# design.net
KiCad netlist of a schematic drawn in Altium Designer
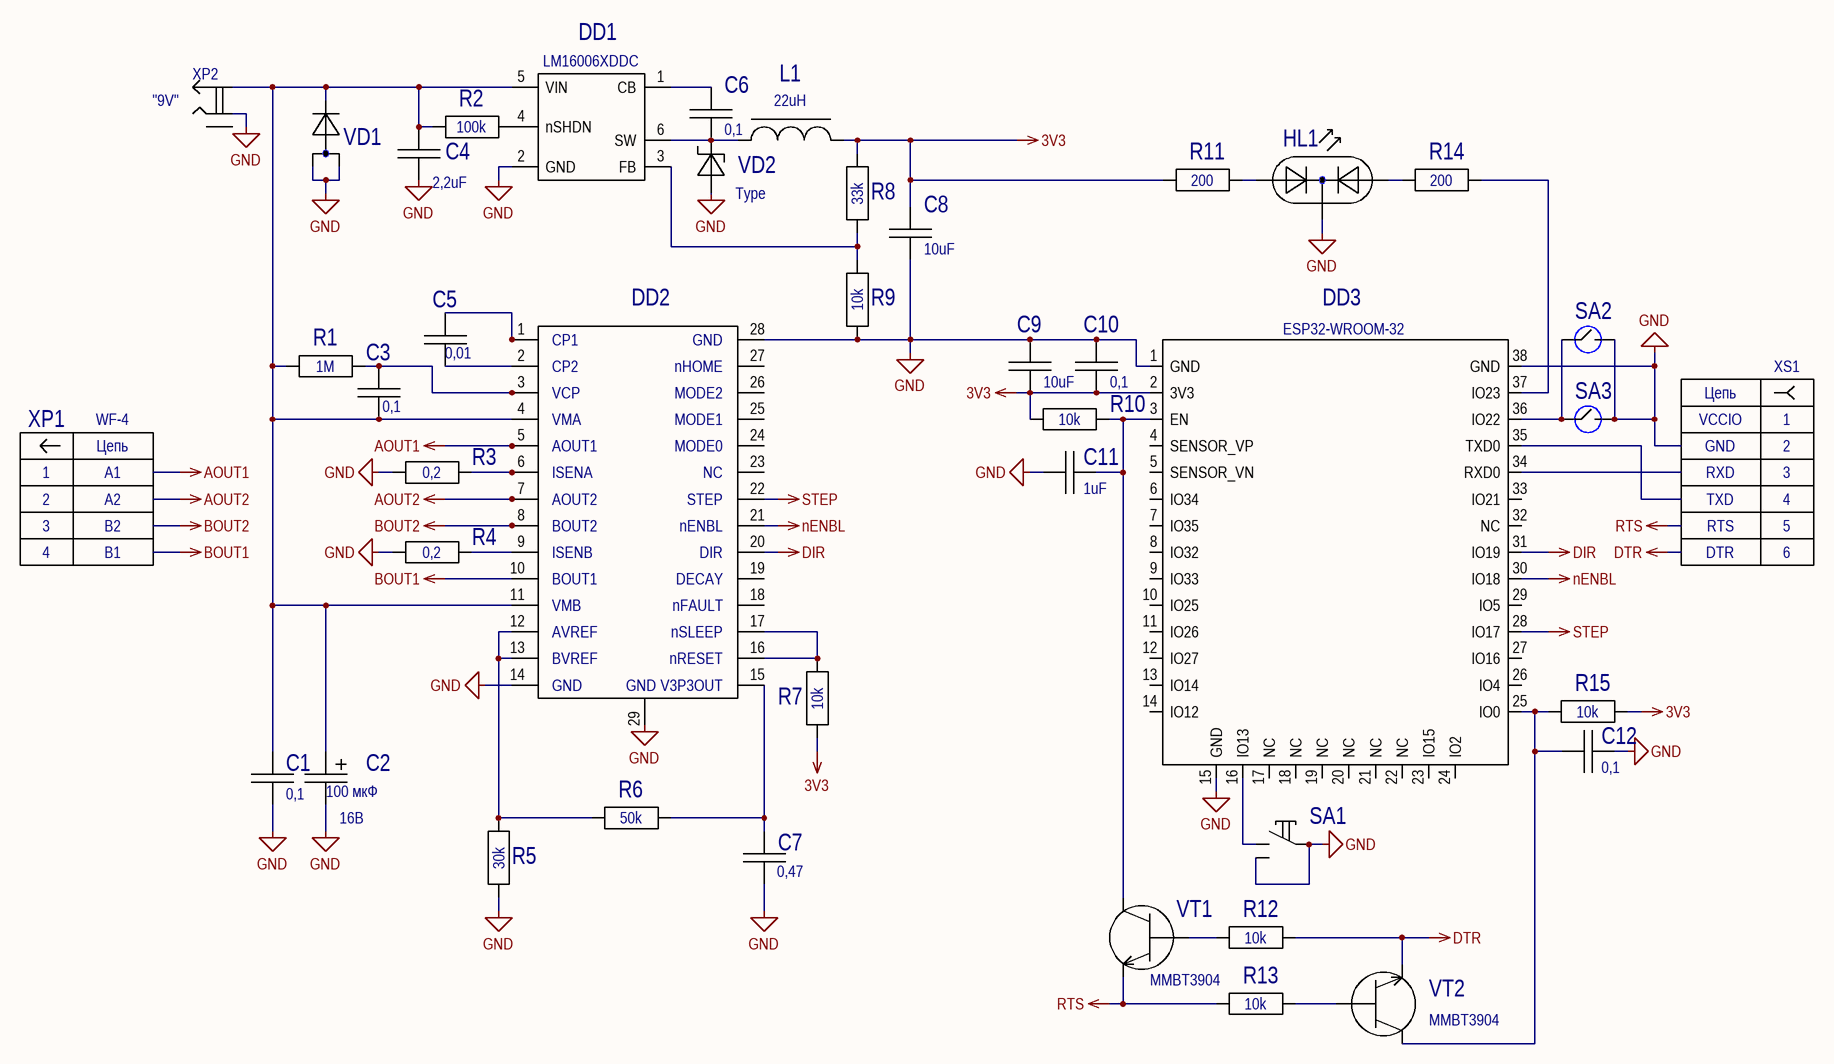
[diagram p0: Схема.SchDoc]

(export (version "E")
  (design (tool "Eeschema 10.0.6"))
  (components
    (comp (ref "C1")
      (value "0,1")
      (footprint "CAPC1608X09N")
      (fields
        (field (name "PART NUMBER") "Конденсатор 0.1мкФ X7R 50В 10% 0603, GRM188R71H104K")
        (field (name "Comment") "C0603")
      )
      (libsource (lib "my_lib") (part "C0603"))
    )
    (comp (ref "C2")
      (value "100 мкФ")
      (footprint "K53-68-E")
      (fields (field (name "VOLT") "16В") (field (name "Comment") "К53-68-E"))
      (libsource (lib "my_lib") (part "К53-68-E"))
    )
    (comp (ref "C3")
      (value "0,1")
      (footprint "CAPC1608X09N")
      (fields
        (field (name "PART NUMBER") "Конденсатор 0.1мкФ X7R 50В 10% 0603, GRM188R71H104K")
        (field (name "Comment") "C0603")
      )
      (libsource (lib "my_lib") (part "C0603"))
    )
    (comp (ref "C4")
      (value "2,2uF")
      (footprint "CAPC2012X14N")
      (fields
        (field (name "PART NUMBER") "Конденсатор 2.2мкФ X7R 25В 0805, GRM21BR71E225K")
        (field (name "Comment") "C0805")
      )
      (libsource (lib "my_lib") (part "C0805"))
    )
    (comp (ref "C5")
      (value "0,01")
      (footprint "CAPC1608X09N")
      (fields
        (field (name "PART NUMBER") "Конденсатор 0.01 мкФ X7R 50В 10% 0603, GRM188R71H103K")
        (field (name "Comment") "C0603")
      )
      (libsource (lib "my_lib") (part "C0603"))
    )
    (comp (ref "C6")
      (value "0,1")
      (footprint "CAPC1608X09N")
      (fields
        (field (name "PART NUMBER") "Конденсатор 0.1мкФ X7R 50В 10% 0603, GRM188R71H104K")
        (field (name "Comment") "C0603")
      )
      (libsource (lib "my_lib") (part "C0603"))
    )
    (comp (ref "C7")
      (value "0,47")
      (footprint "CAPC1608X09N")
      (fields
        (field (name "PART NUMBER") "Конденсатор CC0603KRX7R9BB474, 0603 X7R 0,47мкФ 50В 10%")
        (field (name "Comment") "C0603")
      )
      (libsource (lib "my_lib") (part "C0603"))
    )
    (comp (ref "C8")
      (value "10uF")
      (footprint "CAPC2012X14N")
      (fields
        (field (name "PART NUMBER") "Конденсатор 10 мкФ X5R 10% 16В 0805, GRM21BR61C106K")
        (field (name "Comment") "C0805")
      )
      (libsource (lib "my_lib") (part "C0805"))
    )
    (comp (ref "C9")
      (value "10uF")
      (footprint "CAPC2012X14N")
      (fields
        (field (name "PART NUMBER") "Конденсатор 10 мкФ X5R 10% 16В 0805, GRM21BR61C106K")
        (field (name "Comment") "C0805")
      )
      (libsource (lib "my_lib") (part "C0805"))
    )
    (comp (ref "C10")
      (value "0,1")
      (footprint "CAPC1608X09N")
      (fields
        (field (name "PART NUMBER") "Конденсатор 0.1мкФ X7R 50В 10% 0603, GRM188R71H104K")
        (field (name "Comment") "C0603")
      )
      (libsource (lib "my_lib") (part "C0603"))
    )
    (comp (ref "C11")
      (value "1uF")
      (footprint "CAPC1608X09N")
      (fields
        (field (name "PART NUMBER") "Конденсатор 1мкФ X7R 10В 10% 0603, GRM188R61A105K")
        (field (name "Comment") "C0603")
      )
      (libsource (lib "my_lib") (part "C0603"))
    )
    (comp (ref "C12")
      (value "0,1")
      (footprint "CAPC1608X09N")
      (fields
        (field (name "PART NUMBER") "Конденсатор 0.1мкФ X7R 50В 10% 0603, GRM188R71H104K")
        (field (name "Comment") "C0603")
      )
      (libsource (lib "my_lib") (part "C0603"))
    )
    (comp (ref "DD1")
      (value "LM16006")
      (footprint "TSOP95P280X110-6N")
      (description "LMR16006 SIMPLE SWITCHER® 60 V 0.6 A Buck Regulators")
      (fields
        (field (name "TYPE") "LM16006XDDC")
        (field (name "PART NUMBER") "Микросхема LM16006XDDC")
        (field (name "MANUFACTURER") "Texas Instruments")
      )
      (libsource (lib "my_lib") (part "LM16006XDDC"))
    )
    (comp (ref "DD2")
      (value "DRV8825")
      (footprint "TSOP65P640X120_HS-29N")
      (description "DRV8825 Stepper Motor Controller IC")
      (fields (field (name "PART NUMBER") "DRV8825PWP") (field (name "MANUFACTURER") "Texas Instruments"))
      (libsource (lib "my_lib") (part "DRV8825"))
    )
    (comp (ref "DD3")
      (value "Твердотельное реле 90В, 10А")
      (footprint "ESP32")
      (description "Модуль ESP32")
      (fields
        (field (name "PART NUMBER") "ESP32-WROOM-32D [16MB], Встраиваемый Wi-Fi/Bluetooth модуль на базе чипа ESP32-D0WD с PCB-антенной")
        (field (name "MANUFACTURER") "ESPRESSIV")
        (field (name "TYPE") "ESP32-WROOM-32")
      )
      (libsource (lib "my_lib") (part "ESP32-WROOM-32"))
    )
    (comp (ref "HL1")
      (value "LED3mm3pinCommonCatode")
      (footprint "LED3mm3pinCommonCatode")
      (fields (field (name "PART NUMBER") "Светодиод 3мм двухцветный с общим катодом"))
      (libsource (lib "my_lib") (part "LED3mm3pinCommonCatode"))
    )
    (comp (ref "L1")
      (value "22uH")
      (footprint "INDP7373X45N")
      (description "ЧИП-индуктивность силовая проволочная экранированная 22мкГн +20% 100кГц феррит 1.45А 91мОм")
      (fields
        (field (name "PART NUMBER") "Индуктивность 22uH, 1,45A B82472G6223M000")
        (field (name "Comment") "B82472G6223M000")
      )
      (libsource (lib "my_lib") (part "B82472G6223M000"))
    )
    (comp (ref "R1")
      (value "1M")
      (footprint "RESC1608X06N")
      (description "Резистор 0603")
      (fields (field (name "PART NUMBER") "Резистор 0.1Вт 0603 1 МОм, 5%") (field (name "Comment") "R0603"))
      (libsource (lib "my_lib") (part "R0603"))
    )
    (comp (ref "R2")
      (value "100k")
      (footprint "RESC1608X06N")
      (description "Резистор 0603")
      (fields (field (name "PART NUMBER") "Резистор 0.1Вт 0603 100 кОм, 5%") (field (name "Comment") "R0603"))
      (libsource (lib "my_lib") (part "R0603"))
    )
    (comp (ref "R3")
      (value "0,2")
      (footprint "RESC2012X07N")
      (description "Резистор шунт BOURNS 1W 1% 200 мОм")
      (fields
        (field (name "PART NUMBER") "Резистор 0805 0,2 Ом, 1% RI0805LR200FT")
        (field (name "Comment") "CRL2512-FWR200ELF")
      )
      (libsource (lib "my_lib") (part "CRL2512-FWR200ELF"))
    )
    (comp (ref "R4")
      (value "0,2")
      (footprint "RESC2012X07N")
      (description "Резистор шунт BOURNS 1W 1% 200 мОм")
      (fields
        (field (name "PART NUMBER") "Резистор 0805 0,2 Ом, 1% RI0805LR200FT")
        (field (name "Comment") "CRL2512-FWR200ELF")
      )
      (libsource (lib "my_lib") (part "CRL2512-FWR200ELF"))
    )
    (comp (ref "R5")
      (value "30k")
      (footprint "RESC1608X06N")
      (description "Резистор 0603")
      (fields (field (name "PART NUMBER") "Резистор 0.1Вт 0603 30 кОм, 1%") (field (name "Comment") "R0603"))
      (libsource (lib "my_lib") (part "R0603"))
    )
    (comp (ref "R6")
      (value "50k")
      (footprint "RESC1608X06N")
      (description "Резистор 0603")
      (fields (field (name "PART NUMBER") "Резистор 0.1Вт 0603 50 кОм, 1%") (field (name "Comment") "R0603"))
      (libsource (lib "my_lib") (part "R0603"))
    )
    (comp (ref "R7")
      (value "10k")
      (footprint "RESC1608X06N")
      (description "Резистор 0603")
      (fields (field (name "PART NUMBER") "Резистор 0.1Вт 0603 10 кОм, 5%") (field (name "Comment") "R0603"))
      (libsource (lib "my_lib") (part "R0603"))
    )
    (comp (ref "R8")
      (value "33k")
      (footprint "RESC1608X06N")
      (description "Резистор 0603")
      (fields (field (name "PART NUMBER") "Резистор 0.1Вт 0603 33 кОм, 1%") (field (name "Comment") "R0603"))
      (libsource (lib "my_lib") (part "R0603"))
    )
    (comp (ref "R9")
      (value "10k")
      (footprint "RESC1608X06N")
      (description "Резистор 0603")
      (fields (field (name "PART NUMBER") "Резистор 0.1Вт 0603 10 кОм, 1%") (field (name "Comment") "R0603"))
      (libsource (lib "my_lib") (part "R0603"))
    )
    (comp (ref "R10")
      (value "10k")
      (footprint "RESC1608X06N")
      (description "Резистор 0603")
      (fields (field (name "PART NUMBER") "Резистор 0.1Вт 0603 10 кОм, 5%") (field (name "Comment") "R0603"))
      (libsource (lib "my_lib") (part "R0603"))
    )
    (comp (ref "R11")
      (value "200")
      (footprint "RESC1608X06N")
      (description "Резистор 0603")
      (fields (field (name "PART NUMBER") "Резистор 0.1Вт 0603 200 Ом, 5%") (field (name "Comment") "R0603"))
      (libsource (lib "my_lib") (part "R0603"))
    )
    (comp (ref "R12")
      (value "10k")
      (footprint "RESC1608X06N")
      (description "Резистор 0603")
      (fields (field (name "PART NUMBER") "Резистор 0.1Вт 0603 10 кОм, 5%") (field (name "Comment") "R0603"))
      (libsource (lib "my_lib") (part "R0603"))
    )
    (comp (ref "R13")
      (value "10k")
      (footprint "RESC1608X06N")
      (description "Резистор 0603")
      (fields (field (name "PART NUMBER") "Резистор 0.1Вт 0603 10 кОм, 5%") (field (name "Comment") "R0603"))
      (libsource (lib "my_lib") (part "R0603"))
    )
    (comp (ref "R14")
      (value "200")
      (footprint "RESC1608X06N")
      (description "Резистор 0603")
      (fields (field (name "PART NUMBER") "Резистор 0.1Вт 0603 200 Ом, 5%") (field (name "Comment") "R0603"))
      (libsource (lib "my_lib") (part "R0603"))
    )
    (comp (ref "R15")
      (value "10k")
      (footprint "RESC1608X06N")
      (description "Резистор 0603")
      (fields (field (name "PART NUMBER") "Резистор 0.1Вт 0603 10 кОм, 5%") (field (name "Comment") "R0603"))
      (libsource (lib "my_lib") (part "R0603"))
    )
    (comp (ref "SA1")
      (value "Кнопка")
      (footprint "Кнопка 4,3х4,3 боковая")
      (description "Кнопка трехконтактная 4,5х4,5 боковая")
      (fields (field (name "PART NUMBER") "tact switch 4.5x4.5mm"))
      (libsource (lib "my_lib") (part "TactSwitch4.5x4.5"))
    )
    (comp (ref "SA2")
      (value "геркон 12мм")
      (footprint "Геркон 12 мм")
      (description "Геркон пластик Китай 12мм")
      (fields (field (name "PART NUMBER") "Геркон 12 мм"))
      (libsource (lib "my_lib") (part "геркон 12мм"))
    )
    (comp (ref "SA3")
      (value "геркон 12мм")
      (footprint "Геркон 12 мм")
      (description "Геркон пластик Китай 12мм")
      (fields (field (name "PART NUMBER") "Геркон 12 мм"))
      (libsource (lib "my_lib") (part "геркон 12мм"))
    )
    (comp (ref "VD1")
      (value "SS10PH10")
      (footprint "TO-277A")
      (description "High Current Density Surface-Mount\r\nHigh Voltage Schottky Rectifiers")
      (libsource (lib "my_lib") (part "SS10PH10"))
    )
    (comp (ref "VD2")
      (value "Диод Шоттки 40V, 500mA SOD123")
      (footprint "SODFL370X125-2N")
      (fields (field (name "TYPE") "Type") (field (name "PART NUMBER") "MBR0540"))
      (libsource (lib "my_lib") (part "MBR0540"))
    )
    (comp (ref "VT1")
      (value "MMBT3904")
      (footprint "SOT95P245X110-3N")
      (description "MMBT3904, Транзистор NPN 40В 0.2А [SOT-23-3]")
      (fields (field (name "TYPE") "MMBT3904") (field (name "PART NUMBER") "Транзистор MMBT3904"))
      (libsource (lib "my_lib") (part "MMBT3904"))
    )
    (comp (ref "VT2")
      (value "MMBT3904")
      (footprint "SOT95P245X110-3N")
      (description "MMBT3904, Транзистор NPN 40В 0.2А [SOT-23-3]")
      (fields (field (name "TYPE") "MMBT3904") (field (name "PART NUMBER") "Транзистор MMBT3904"))
      (libsource (lib "my_lib") (part "MMBT3904"))
    )
    (comp (ref "XP1")
      (value "WF4")
      (footprint "WF-4")
      (description "Вилка 2,54мм прямая на плату")
      (fields (field (name "TYPE") "WF-4") (field (name "PART NUMBER") "Вилка WF-4"))
      (libsource (lib "soed_new") (part "WF4_1"))
    )
    (comp (ref "XP2")
      (value "DC-005")
      (footprint "DC-005")
      (description "Разъем питания DC 2.1x5.5 мм гнездо, прямой угол на плату")
      (fields (field (name "PART NUMBER") "Вилка DS-201"))
      (libsource (lib "soed_new") (part "DC-005"))
    )
    (comp (ref "XS1")
      (value "PBS-6R")
      (footprint "PBS-6")
      (description "Розетка 2,54мм прямая однорядная на плату")
      (fields (field (name "PART NUMBER") "Розетка PBS-6"))
      (libsource (lib "soed_new") (part "PBS-6"))
    )
  )
  (nets
    (net (code "1") (name "3V3") (class "Default")
      (node (ref "C10") (pin "1") (pinfunction "1_1") (pintype "passive"))
      (node (ref "C8") (pin "1") (pinfunction "0_1") (pintype "passive"))
      (node (ref "C9") (pin "2") (pinfunction "1_2") (pintype "passive"))
      (node (ref "DD3") (pin "2") (pinfunction "3V3_2") (pintype "passive"))
      (node (ref "L1") (pin "1") (pinfunction "0_1") (pintype "passive"))
      (node (ref "R10") (pin "2") (pinfunction "2_2") (pintype "passive"))
      (node (ref "R11") (pin "2") (pinfunction "2_2") (pintype "passive"))
      (node (ref "R15") (pin "1") (pinfunction "1_1") (pintype "passive"))
      (node (ref "R7") (pin "1") (pinfunction "1_1") (pintype "passive"))
      (node (ref "R8") (pin "2") (pinfunction "2_2") (pintype "passive"))
    )
    (net (code "2") (name "AOUT1") (class "Default")
      (node (ref "DD2") (pin "5") (pinfunction "5_5") (pintype "passive"))
      (node (ref "XP1") (pin "1") (pinfunction "1_1") (pintype "passive"))
    )
    (net (code "3") (name "AOUT2") (class "Default")
      (node (ref "DD2") (pin "7") (pinfunction "7_7") (pintype "passive"))
      (node (ref "XP1") (pin "2") (pinfunction "2_2") (pintype "passive"))
    )
    (net (code "4") (name "BOUT1") (class "Default")
      (node (ref "DD2") (pin "10") (pinfunction "10_10") (pintype "passive"))
      (node (ref "XP1") (pin "4") (pinfunction "4_4") (pintype "passive"))
    )
    (net (code "5") (name "BOUT2") (class "Default")
      (node (ref "DD2") (pin "8") (pinfunction "8_8") (pintype "passive"))
      (node (ref "XP1") (pin "3") (pinfunction "3_3") (pintype "passive"))
    )
    (net (code "6") (name "DIR") (class "Default")
      (node (ref "DD2") (pin "20") (pinfunction "20_20") (pintype "passive"))
      (node (ref "DD3") (pin "31") (pinfunction "IO19_31") (pintype "passive"))
    )
    (net (code "7") (name "DTR") (class "Default")
      (node (ref "R12") (pin "2") (pinfunction "2_2") (pintype "passive"))
      (node (ref "VT2") (pin "2") (pinfunction "E_2") (pintype "passive"))
      (node (ref "XS1") (pin "6") (pinfunction "6_6") (pintype "passive"))
    )
    (net (code "8") (name "GND") (class "Default")
      (node (ref "C1") (pin "1") (pinfunction "1_1") (pintype "passive"))
      (node (ref "C10") (pin "2") (pinfunction "2_2") (pintype "passive"))
      (node (ref "C11") (pin "1") (pinfunction "1_1") (pintype "passive"))
      (node (ref "C12") (pin "2") (pinfunction "2_2") (pintype "passive"))
      (node (ref "C2") (pin "2") (pinfunction "2_2") (pintype "passive"))
      (node (ref "C4") (pin "2") (pinfunction "1_2") (pintype "passive"))
      (node (ref "C7") (pin "2") (pinfunction "2_2") (pintype "passive"))
      (node (ref "C8") (pin "2") (pinfunction "1_2") (pintype "passive"))
      (node (ref "C9") (pin "1") (pinfunction "0_1") (pintype "passive"))
      (node (ref "DD1") (pin "2") (pinfunction "GND_2") (pintype "passive"))
      (node (ref "DD2") (pin "14") (pinfunction "14_14") (pintype "passive"))
      (node (ref "DD2") (pin "28") (pinfunction "28_28") (pintype "passive"))
      (node (ref "DD2") (pin "29") (pinfunction "29_29") (pintype "passive"))
      (node (ref "DD3") (pin "1") (pinfunction "GND_1") (pintype "passive"))
      (node (ref "DD3") (pin "15") (pinfunction "GND_15") (pintype "passive"))
      (node (ref "DD3") (pin "38") (pinfunction "GND_38") (pintype "passive"))
      (node (ref "HL1") (pin "3") (pinfunction "C_3") (pintype "passive"))
      (node (ref "R3") (pin "1") (pinfunction "1_1") (pintype "passive"))
      (node (ref "R4") (pin "1") (pinfunction "1_1") (pintype "passive"))
      (node (ref "R5") (pin "1") (pinfunction "1_1") (pintype "passive"))
      (node (ref "R9") (pin "1") (pinfunction "1_1") (pintype "passive"))
      (node (ref "SA1") (pin "1") (pinfunction "1_1") (pintype "passive"))
      (node (ref "SA1") (pin "3") (pinfunction "3_3") (pintype "passive"))
      (node (ref "SA2") (pin "2") (pinfunction "2_2") (pintype "passive"))
      (node (ref "SA3") (pin "2") (pinfunction "2_2") (pintype "passive"))
      (node (ref "VD1") (pin "1") (pinfunction "A1_1") (pintype "passive"))
      (node (ref "VD1") (pin "2") (pinfunction "A2_2") (pintype "passive"))
      (node (ref "VD2") (pin "1") (pinfunction "1_1") (pintype "passive"))
      (node (ref "XP2") (pin "2") (pinfunction "2_2") (pintype "passive"))
      (node (ref "XS1") (pin "2") (pinfunction "2_2") (pintype "passive"))
    )
    (net (code "9") (name "Net-(C3-Pad2)") (class "Default")
      (node (ref "C3") (pin "2") (pinfunction "2_2") (pintype "passive"))
      (node (ref "DD2") (pin "3") (pinfunction "3_3") (pintype "passive"))
      (node (ref "R1") (pin "2") (pinfunction "2_2") (pintype "passive"))
    )
    (net (code "10") (name "Net-(C4-0)") (class "Default")
      (node (ref "C1") (pin "2") (pinfunction "2_2") (pintype "passive"))
      (node (ref "C2") (pin "1") (pinfunction "1_1") (pintype "passive"))
      (node (ref "C3") (pin "1") (pinfunction "1_1") (pintype "passive"))
      (node (ref "C4") (pin "1") (pinfunction "0_1") (pintype "passive"))
      (node (ref "DD1") (pin "5") (pinfunction "VIN_5") (pintype "passive"))
      (node (ref "DD2") (pin "11") (pinfunction "11_11") (pintype "passive"))
      (node (ref "DD2") (pin "4") (pinfunction "4_4") (pintype "passive"))
      (node (ref "R1") (pin "1") (pinfunction "1_1") (pintype "passive"))
      (node (ref "R2") (pin "1") (pinfunction "1_1") (pintype "passive"))
      (node (ref "VD1") (pin "3") (pinfunction "C_3") (pintype "passive"))
      (node (ref "XP2") (pin "1") (pinfunction "1_1") (pintype "passive"))
    )
    (net (code "11") (name "Net-(C5-Pad1)") (class "Default")
      (node (ref "C5") (pin "1") (pinfunction "1_1") (pintype "passive"))
      (node (ref "DD2") (pin "1") (pinfunction "1_1") (pintype "passive"))
    )
    (net (code "12") (name "Net-(C5-Pad2)") (class "Default")
      (node (ref "C5") (pin "2") (pinfunction "2_2") (pintype "passive"))
      (node (ref "DD2") (pin "2") (pinfunction "2_2") (pintype "passive"))
    )
    (net (code "13") (name "Net-(C7-Pad1)") (class "Default")
      (node (ref "C7") (pin "1") (pinfunction "1_1") (pintype "passive"))
      (node (ref "DD2") (pin "15") (pinfunction "15_15") (pintype "passive"))
      (node (ref "R6") (pin "2") (pinfunction "2_2") (pintype "passive"))
    )
    (net (code "14") (name "Net-(DD1-CB)") (class "Default")
      (node (ref "C6") (pin "1") (pinfunction "1_1") (pintype "passive"))
      (node (ref "DD1") (pin "1") (pinfunction "CB_1") (pintype "passive"))
    )
    (net (code "15") (name "Net-(DD1-FB)") (class "Default")
      (node (ref "DD1") (pin "3") (pinfunction "FB_3") (pintype "passive"))
      (node (ref "R8") (pin "1") (pinfunction "1_1") (pintype "passive"))
      (node (ref "R9") (pin "2") (pinfunction "2_2") (pintype "passive"))
    )
    (net (code "16") (name "Net-(DD1-SW)") (class "Default")
      (node (ref "C6") (pin "2") (pinfunction "2_2") (pintype "passive"))
      (node (ref "DD1") (pin "6") (pinfunction "SW_6") (pintype "passive"))
      (node (ref "L1") (pin "2") (pinfunction "1_2") (pintype "passive"))
      (node (ref "VD2") (pin "2") (pinfunction "2_2") (pintype "passive"))
    )
    (net (code "17") (name "Net-(DD1-nSHDN)") (class "Default")
      (node (ref "DD1") (pin "4") (pinfunction "nSHDN_4") (pintype "passive"))
      (node (ref "R2") (pin "2") (pinfunction "2_2") (pintype "passive"))
    )
    (net (code "18") (name "Net-(DD2-Pad6)") (class "Default")
      (node (ref "DD2") (pin "6") (pinfunction "6_6") (pintype "passive"))
      (node (ref "R3") (pin "2") (pinfunction "2_2") (pintype "passive"))
    )
    (net (code "19") (name "Net-(DD2-Pad9)") (class "Default")
      (node (ref "DD2") (pin "9") (pinfunction "9_9") (pintype "passive"))
      (node (ref "R4") (pin "2") (pinfunction "2_2") (pintype "passive"))
    )
    (net (code "20") (name "Net-(DD2-Pad12)") (class "Default")
      (node (ref "DD2") (pin "12") (pinfunction "12_12") (pintype "passive"))
      (node (ref "DD2") (pin "13") (pinfunction "13_13") (pintype "passive"))
      (node (ref "R5") (pin "2") (pinfunction "2_2") (pintype "passive"))
      (node (ref "R6") (pin "1") (pinfunction "1_1") (pintype "passive"))
    )
    (net (code "21") (name "Net-(DD2-Pad16)") (class "Default")
      (node (ref "DD2") (pin "16") (pinfunction "16_16") (pintype "passive"))
      (node (ref "DD2") (pin "17") (pinfunction "17_17") (pintype "passive"))
      (node (ref "R7") (pin "2") (pinfunction "2_2") (pintype "passive"))
    )
    (net (code "22") (name "Net-(DD3-EN)") (class "Default")
      (node (ref "C11") (pin "2") (pinfunction "2_2") (pintype "passive"))
      (node (ref "DD3") (pin "3") (pinfunction "EN_3") (pintype "passive"))
      (node (ref "R10") (pin "1") (pinfunction "1_1") (pintype "passive"))
      (node (ref "VT1") (pin "3") (pinfunction "C_3") (pintype "passive"))
    )
    (net (code "23") (name "Net-(DD3-IO0)") (class "Default")
      (node (ref "C12") (pin "1") (pinfunction "1_1") (pintype "passive"))
      (node (ref "DD3") (pin "25") (pinfunction "IO0_25") (pintype "passive"))
      (node (ref "R15") (pin "2") (pinfunction "2_2") (pintype "passive"))
      (node (ref "VT2") (pin "3") (pinfunction "C_3") (pintype "passive"))
    )
    (net (code "24") (name "Net-(DD3-IO13)") (class "Default")
      (node (ref "DD3") (pin "16") (pinfunction "IO13_16") (pintype "passive"))
      (node (ref "SA1") (pin "2") (pinfunction "2_2") (pintype "passive"))
    )
    (net (code "25") (name "Net-(DD3-IO22)") (class "Default")
      (node (ref "DD3") (pin "36") (pinfunction "IO22_36") (pintype "passive"))
      (node (ref "SA2") (pin "1") (pinfunction "1_1") (pintype "passive"))
      (node (ref "SA3") (pin "1") (pinfunction "1_1") (pintype "passive"))
    )
    (net (code "26") (name "Net-(DD3-IO23)") (class "Default")
      (node (ref "DD3") (pin "37") (pinfunction "IO23_37") (pintype "passive"))
      (node (ref "R14") (pin "1") (pinfunction "1_1") (pintype "passive"))
    )
    (net (code "27") (name "Net-(DD3-RXD0)") (class "Default")
      (node (ref "DD3") (pin "34") (pinfunction "RXD0_34") (pintype "passive"))
      (node (ref "XS1") (pin "3") (pinfunction "3_3") (pintype "passive"))
    )
    (net (code "28") (name "Net-(DD3-TXD0)") (class "Default")
      (node (ref "DD3") (pin "35") (pinfunction "TXD0_35") (pintype "passive"))
      (node (ref "XS1") (pin "4") (pinfunction "4_4") (pintype "passive"))
    )
    (net (code "29") (name "Net-(HL1-A1)") (class "Default")
      (node (ref "HL1") (pin "1") (pinfunction "A1_1") (pintype "passive"))
      (node (ref "R11") (pin "1") (pinfunction "1_1") (pintype "passive"))
    )
    (net (code "30") (name "Net-(HL1-A2)") (class "Default")
      (node (ref "HL1") (pin "2") (pinfunction "A2_2") (pintype "passive"))
      (node (ref "R14") (pin "2") (pinfunction "2_2") (pintype "passive"))
    )
    (net (code "31") (name "Net-(VT1-B)") (class "Default")
      (node (ref "R12") (pin "1") (pinfunction "1_1") (pintype "passive"))
      (node (ref "VT1") (pin "1") (pinfunction "B_1") (pintype "passive"))
    )
    (net (code "32") (name "Net-(VT2-B)") (class "Default")
      (node (ref "R13") (pin "2") (pinfunction "2_2") (pintype "passive"))
      (node (ref "VT2") (pin "1") (pinfunction "B_1") (pintype "passive"))
    )
    (net (code "33") (name "RTS") (class "Default")
      (node (ref "R13") (pin "1") (pinfunction "1_1") (pintype "passive"))
      (node (ref "VT1") (pin "2") (pinfunction "E_2") (pintype "passive"))
      (node (ref "XS1") (pin "5") (pinfunction "5_5") (pintype "passive"))
    )
    (net (code "34") (name "STEP") (class "Default")
      (node (ref "DD2") (pin "22") (pinfunction "22_22") (pintype "passive"))
      (node (ref "DD3") (pin "28") (pinfunction "IO17_28") (pintype "passive"))
    )
    (net (code "35") (name "nENBL") (class "Default")
      (node (ref "DD2") (pin "21") (pinfunction "21_21") (pintype "passive"))
      (node (ref "DD3") (pin "30") (pinfunction "IO18_30") (pintype "passive"))
    )
    (net (code "36") (name "unconnected-(DD2-Pad19)") (class "Default")
      (node (ref "DD2") (pin "19") (pinfunction "19_19") (pintype "passive"))
    )
    (net (code "37") (name "unconnected-(DD2-Pad23)") (class "Default")
      (node (ref "DD2") (pin "23") (pinfunction "23_23") (pintype "passive"))
    )
    (net (code "38") (name "unconnected-(DD2-Pad24)") (class "Default")
      (node (ref "DD2") (pin "24") (pinfunction "24_24") (pintype "passive"))
    )
    (net (code "39") (name "unconnected-(DD2-Pad25)") (class "Default")
      (node (ref "DD2") (pin "25") (pinfunction "25_25") (pintype "passive"))
    )
    (net (code "40") (name "unconnected-(DD2-Pad26)") (class "Default")
      (node (ref "DD2") (pin "26") (pinfunction "26_26") (pintype "passive"))
    )
    (net (code "41") (name "unconnected-(DD2-Pad27)") (class "Default")
      (node (ref "DD2") (pin "27") (pinfunction "27_27") (pintype "passive"))
    )
    (net (code "42") (name "unconnected-(DD2-REFIN2+{slash}AUN4+-Pad18)") (class "Default")
      (node (ref "DD2") (pin "18") (pinfunction "REFIN2+/AUN4+_18") (pintype "passive"))
    )
    (net (code "43") (name "unconnected-(DD3-IO2-Pad24)") (class "Default")
      (node (ref "DD3") (pin "24") (pinfunction "IO2_24") (pintype "passive"))
    )
    (net (code "44") (name "unconnected-(DD3-IO4-Pad26)") (class "Default")
      (node (ref "DD3") (pin "26") (pinfunction "IO4_26") (pintype "passive"))
    )
    (net (code "45") (name "unconnected-(DD3-IO5-Pad29)") (class "Default")
      (node (ref "DD3") (pin "29") (pinfunction "IO5_29") (pintype "passive"))
    )
    (net (code "46") (name "unconnected-(DD3-IO12-Pad14)") (class "Default")
      (node (ref "DD3") (pin "14") (pinfunction "IO12_14") (pintype "passive"))
    )
    (net (code "47") (name "unconnected-(DD3-IO14-Pad13)") (class "Default")
      (node (ref "DD3") (pin "13") (pinfunction "IO14_13") (pintype "passive"))
    )
    (net (code "48") (name "unconnected-(DD3-IO15-Pad23)") (class "Default")
      (node (ref "DD3") (pin "23") (pinfunction "IO15_23") (pintype "passive"))
    )
    (net (code "49") (name "unconnected-(DD3-IO16-Pad27)") (class "Default")
      (node (ref "DD3") (pin "27") (pinfunction "IO16_27") (pintype "passive"))
    )
    (net (code "50") (name "unconnected-(DD3-IO21-Pad33)") (class "Default")
      (node (ref "DD3") (pin "33") (pinfunction "IO21_33") (pintype "passive"))
    )
    (net (code "51") (name "unconnected-(DD3-IO25-Pad10)") (class "Default")
      (node (ref "DD3") (pin "10") (pinfunction "IO25_10") (pintype "passive"))
    )
    (net (code "52") (name "unconnected-(DD3-IO26-Pad11)") (class "Default")
      (node (ref "DD3") (pin "11") (pinfunction "IO26_11") (pintype "passive"))
    )
    (net (code "53") (name "unconnected-(DD3-IO27-Pad12)") (class "Default")
      (node (ref "DD3") (pin "12") (pinfunction "IO27_12") (pintype "passive"))
    )
    (net (code "54") (name "unconnected-(DD3-IO32-Pad8)") (class "Default")
      (node (ref "DD3") (pin "8") (pinfunction "IO32_8") (pintype "passive"))
    )
    (net (code "55") (name "unconnected-(DD3-IO33-Pad9)") (class "Default")
      (node (ref "DD3") (pin "9") (pinfunction "IO33_9") (pintype "passive"))
    )
    (net (code "56") (name "unconnected-(DD3-IO34-Pad6)") (class "Default")
      (node (ref "DD3") (pin "6") (pinfunction "IO34_6") (pintype "passive"))
    )
    (net (code "57") (name "unconnected-(DD3-IO35-Pad7)") (class "Default")
      (node (ref "DD3") (pin "7") (pinfunction "IO35_7") (pintype "passive"))
    )
    (net (code "58") (name "unconnected-(DD3-NC-Pad17)") (class "Default")
      (node (ref "DD3") (pin "17") (pinfunction "NC_17") (pintype "passive"))
    )
    (net (code "59") (name "unconnected-(DD3-NC-Pad18)") (class "Default")
      (node (ref "DD3") (pin "18") (pinfunction "NC_18") (pintype "passive"))
    )
    (net (code "60") (name "unconnected-(DD3-NC-Pad19)") (class "Default")
      (node (ref "DD3") (pin "19") (pinfunction "NC_19") (pintype "passive"))
    )
    (net (code "61") (name "unconnected-(DD3-NC-Pad20)") (class "Default")
      (node (ref "DD3") (pin "20") (pinfunction "NC_20") (pintype "passive"))
    )
    (net (code "62") (name "unconnected-(DD3-NC-Pad21)") (class "Default")
      (node (ref "DD3") (pin "21") (pinfunction "NC_21") (pintype "passive"))
    )
    (net (code "63") (name "unconnected-(DD3-NC-Pad22)") (class "Default")
      (node (ref "DD3") (pin "22") (pinfunction "NC_22") (pintype "passive"))
    )
    (net (code "64") (name "unconnected-(DD3-NC-Pad32)") (class "Default")
      (node (ref "DD3") (pin "32") (pinfunction "NC_32") (pintype "passive"))
    )
    (net (code "65") (name "unconnected-(DD3-SENSOR_VN-Pad5)") (class "Default")
      (node (ref "DD3") (pin "5") (pinfunction "SENSOR_VN_5") (pintype "passive"))
    )
    (net (code "66") (name "unconnected-(DD3-SENSOR_VP-Pad4)") (class "Default")
      (node (ref "DD3") (pin "4") (pinfunction "SENSOR_VP_4") (pintype "passive"))
    )
    (net (code "67") (name "unconnected-(XP2-Pad3)") (class "Default")
      (node (ref "XP2") (pin "3") (pinfunction "3_3") (pintype "passive"))
    )
    (net (code "68") (name "unconnected-(XS1-Pad1)") (class "Default")
      (node (ref "XS1") (pin "1") (pinfunction "1_1") (pintype "passive"))
    )
  )
)
